# RearBreakoutSchematic.net
KiCad netlist of a schematic drawn in Altium Designer
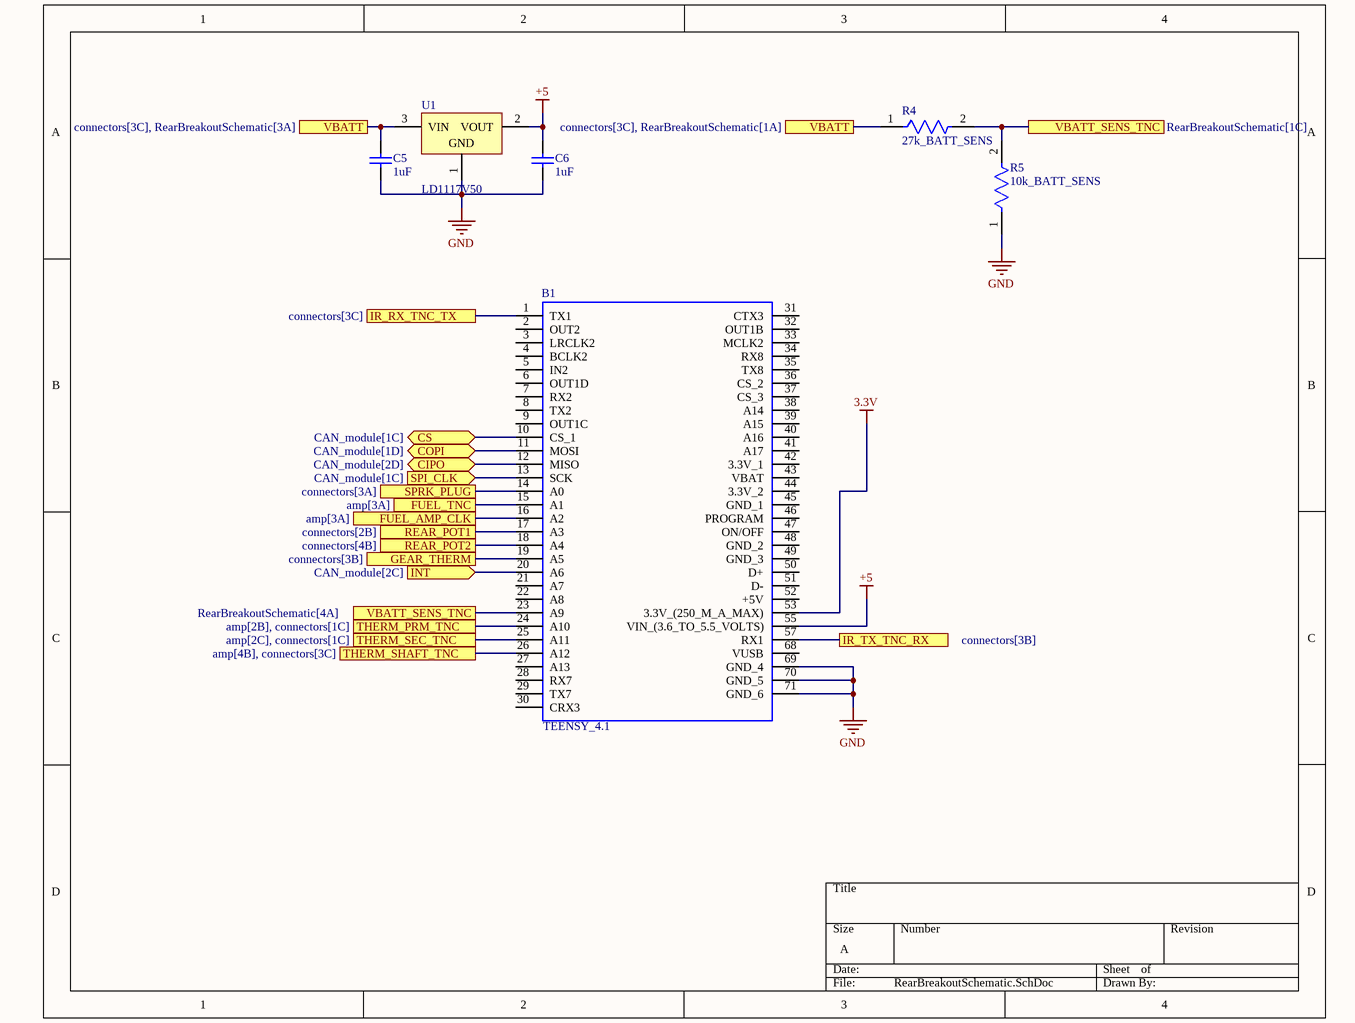
[diagram p0: RearBreakoutSchematic.SchDoc]

(export (version "E")
  (design (tool "Eeschema 10.0.6"))
  (components
    (comp (ref "B1")
      (value "TEENSY_4.1")
      (footprint "TEENSY41")
      (description "Teensy 4.1 Development Board")
      (fields (field (name "MANUFACTURER_PART_NUMBER") "TEENSY 4.1"))
      (libsource (lib "TEENSY_4.1") (part "TEENSY_4.1"))
    )
    (comp (ref "C5")
      (value "1uF")
      (footprint "CAPC2013X145X50LL20T25")
      (description "C0805C105K4PACTU")
      (fields (field (name "MANUFACTURER") "Kemet"))
      (libsource (lib "Altium Content Vault") (part "CAP"))
    )
    (comp (ref "C6")
      (value "1uF")
      (footprint "CAPC2013X145X50LL20T25")
      (description "C0805C105K4PACTU")
      (fields (field (name "MANUFACTURER") "Kemet"))
      (libsource (lib "Altium Content Vault") (part "CAP"))
    )
    (comp (ref "R4")
      (value "27k_BATT_SENS")
      (footprint "FP-CRCW0805-e3-IPC_C")
      (description "RES Thick Film, 4.02Ω, 1%, 0.125W, 200ppm/°C, 0805")
      (fields (field (name "TOLERANCE") "1%"))
      (libsource (lib "Altium Content Vault") (part "1029c3af85768c4190bb7ad29bc67b5"))
    )
    (comp (ref "R5")
      (value "10k_BATT_SENS")
      (footprint "FP-CRCW0805-e3-IPC_C")
      (description "RES Thick Film, 4.02Ω, 1%, 0.125W, 200ppm/°C, 0805")
      (fields (field (name "TOLERANCE") "1%"))
      (libsource (lib "Altium Content Vault") (part "1029c3af85768c4190bb7ad29bc67b5"))
    )
    (comp (ref "U1")
      (value "LD1117V50")
      (footprint "TO220")
      (description "Fixed Low Drop Positive Voltage Regulator, 5V, 3-Pin TO-220")
      (libsource (lib "Altium Content Vault") (part "PM-REG-LD1117V-SIL3"))
    )
  )
  (nets
    (net (code "1") (name "+5") (class "Default")
      (node (ref "B1") (pin "55") (pinfunction "VIN_(3.6_TO_5.5_VOLTS)_55") (pintype "passive"))
      (node (ref "C6") (pin "2") (pinfunction "2_2") (pintype "passive"))
      (node (ref "U1") (pin "2") (pinfunction "VOUT_2") (pintype "power_in"))
    )
    (net (code "2") (name "/CIPO") (class "Default")
      (node (ref "B1") (pin "12") (pinfunction "MISO_12") (pintype "passive"))
    )
    (net (code "3") (name "/COPI") (class "Default")
      (node (ref "B1") (pin "11") (pinfunction "MOSI_11") (pintype "passive"))
    )
    (net (code "4") (name "/CS") (class "Default")
      (node (ref "B1") (pin "10") (pinfunction "CS_1_10") (pintype "passive"))
    )
    (net (code "5") (name "/FUEL_AMP_CLK") (class "Default")
      (node (ref "B1") (pin "16") (pinfunction "A2_16") (pintype "passive"))
    )
    (net (code "6") (name "/FUEL_TNC") (class "Default")
      (node (ref "B1") (pin "15") (pinfunction "A1_15") (pintype "passive"))
    )
    (net (code "7") (name "/GEAR_THERM") (class "Default")
      (node (ref "B1") (pin "19") (pinfunction "A5_19") (pintype "passive"))
    )
    (net (code "8") (name "/INT") (class "Default")
      (node (ref "B1") (pin "20") (pinfunction "A6_20") (pintype "passive"))
    )
    (net (code "9") (name "/IR_RX_TNC_TX") (class "Default")
      (node (ref "B1") (pin "1") (pinfunction "TX1_1") (pintype "passive"))
    )
    (net (code "10") (name "/IR_TX_TNC_RX") (class "Default")
      (node (ref "B1") (pin "57") (pinfunction "RX1_57") (pintype "passive"))
    )
    (net (code "11") (name "/REAR_POT1") (class "Default")
      (node (ref "B1") (pin "17") (pinfunction "A3_17") (pintype "passive"))
    )
    (net (code "12") (name "/REAR_POT2") (class "Default")
      (node (ref "B1") (pin "18") (pinfunction "A4_18") (pintype "passive"))
    )
    (net (code "13") (name "/SPI_CLK") (class "Default")
      (node (ref "B1") (pin "13") (pinfunction "SCK_13") (pintype "passive"))
    )
    (net (code "14") (name "/SPRK_PLUG") (class "Default")
      (node (ref "B1") (pin "14") (pinfunction "A0_14") (pintype "passive"))
    )
    (net (code "15") (name "/THERM_PRM_TNC") (class "Default")
      (node (ref "B1") (pin "24") (pinfunction "A10_24") (pintype "passive"))
    )
    (net (code "16") (name "/THERM_SEC_TNC") (class "Default")
      (node (ref "B1") (pin "25") (pinfunction "A11_25") (pintype "passive"))
    )
    (net (code "17") (name "/THERM_SHAFT_TNC") (class "Default")
      (node (ref "B1") (pin "26") (pinfunction "A12_26") (pintype "passive"))
    )
    (net (code "18") (name "/VBATT") (class "Default")
      (node (ref "C5") (pin "2") (pinfunction "2_2") (pintype "passive"))
      (node (ref "R4") (pin "1") (pinfunction "1_1") (pintype "passive"))
      (node (ref "U1") (pin "3") (pinfunction "VIN_3") (pintype "power_in"))
    )
    (net (code "19") (name "/VBATT_SENS_TNC") (class "Default")
      (node (ref "B1") (pin "23") (pinfunction "A9_23") (pintype "passive"))
      (node (ref "R4") (pin "2") (pinfunction "2_2") (pintype "passive"))
      (node (ref "R5") (pin "2") (pinfunction "2_2") (pintype "passive"))
    )
    (net (code "20") (name "3.3V") (class "Default")
      (node (ref "B1") (pin "53") (pinfunction "3.3V_(250_M_A_MAX)_53") (pintype "passive"))
    )
    (net (code "21") (name "GND") (class "Default")
      (node (ref "B1") (pin "69") (pinfunction "GND_4_69") (pintype "passive"))
      (node (ref "B1") (pin "70") (pinfunction "GND_5_70") (pintype "passive"))
      (node (ref "B1") (pin "71") (pinfunction "GND_6_71") (pintype "passive"))
      (node (ref "C5") (pin "1") (pinfunction "1_1") (pintype "passive"))
      (node (ref "C6") (pin "1") (pinfunction "1_1") (pintype "passive"))
      (node (ref "R5") (pin "1") (pinfunction "1_1") (pintype "passive"))
      (node (ref "U1") (pin "1") (pinfunction "GND_1") (pintype "power_in"))
    )
    (net (code "22") (name "unconnected-(B1-+5V-Pad52)") (class "Default")
      (node (ref "B1") (pin "52") (pinfunction "+5V_52") (pintype "passive"))
    )
    (net (code "23") (name "unconnected-(B1-3.3V_1-Pad42)") (class "Default")
      (node (ref "B1") (pin "42") (pinfunction "3.3V_1_42") (pintype "passive"))
    )
    (net (code "24") (name "unconnected-(B1-3.3V_2-Pad44)") (class "Default")
      (node (ref "B1") (pin "44") (pinfunction "3.3V_2_44") (pintype "passive"))
    )
    (net (code "25") (name "unconnected-(B1-A7-Pad21)") (class "Default")
      (node (ref "B1") (pin "21") (pinfunction "A7_21") (pintype "passive"))
    )
    (net (code "26") (name "unconnected-(B1-A8-Pad22)") (class "Default")
      (node (ref "B1") (pin "22") (pinfunction "A8_22") (pintype "passive"))
    )
    (net (code "27") (name "unconnected-(B1-A13-Pad27)") (class "Default")
      (node (ref "B1") (pin "27") (pinfunction "A13_27") (pintype "passive"))
    )
    (net (code "28") (name "unconnected-(B1-A14-Pad38)") (class "Default")
      (node (ref "B1") (pin "38") (pinfunction "A14_38") (pintype "passive"))
    )
    (net (code "29") (name "unconnected-(B1-A15-Pad39)") (class "Default")
      (node (ref "B1") (pin "39") (pinfunction "A15_39") (pintype "passive"))
    )
    (net (code "30") (name "unconnected-(B1-A16-Pad40)") (class "Default")
      (node (ref "B1") (pin "40") (pinfunction "A16_40") (pintype "passive"))
    )
    (net (code "31") (name "unconnected-(B1-A17-Pad41)") (class "Default")
      (node (ref "B1") (pin "41") (pinfunction "A17_41") (pintype "passive"))
    )
    (net (code "32") (name "unconnected-(B1-BCLK2-Pad4)") (class "Default")
      (node (ref "B1") (pin "4") (pinfunction "BCLK2_4") (pintype "passive"))
    )
    (net (code "33") (name "unconnected-(B1-CRX3-Pad30)") (class "Default")
      (node (ref "B1") (pin "30") (pinfunction "CRX3_30") (pintype "passive"))
    )
    (net (code "34") (name "unconnected-(B1-CS_2-Pad36)") (class "Default")
      (node (ref "B1") (pin "36") (pinfunction "CS_2_36") (pintype "passive"))
    )
    (net (code "35") (name "unconnected-(B1-CS_3-Pad37)") (class "Default")
      (node (ref "B1") (pin "37") (pinfunction "CS_3_37") (pintype "passive"))
    )
    (net (code "36") (name "unconnected-(B1-CTX3-Pad31)") (class "Default")
      (node (ref "B1") (pin "31") (pinfunction "CTX3_31") (pintype "passive"))
    )
    (net (code "37") (name "unconnected-(B1-D+-Pad50)") (class "Default")
      (node (ref "B1") (pin "50") (pinfunction "D+_50") (pintype "passive"))
    )
    (net (code "38") (name "unconnected-(B1-D--Pad51)") (class "Default")
      (node (ref "B1") (pin "51") (pinfunction "D-_51") (pintype "passive"))
    )
    (net (code "39") (name "unconnected-(B1-GND_1-Pad45)") (class "Default")
      (node (ref "B1") (pin "45") (pinfunction "GND_1_45") (pintype "passive"))
    )
    (net (code "40") (name "unconnected-(B1-GND_2-Pad48)") (class "Default")
      (node (ref "B1") (pin "48") (pinfunction "GND_2_48") (pintype "passive"))
    )
    (net (code "41") (name "unconnected-(B1-GND_3-Pad49)") (class "Default")
      (node (ref "B1") (pin "49") (pinfunction "GND_3_49") (pintype "passive"))
    )
    (net (code "42") (name "unconnected-(B1-IN2-Pad5)") (class "Default")
      (node (ref "B1") (pin "5") (pinfunction "IN2_5") (pintype "passive"))
    )
    (net (code "43") (name "unconnected-(B1-LRCLK2-Pad3)") (class "Default")
      (node (ref "B1") (pin "3") (pinfunction "LRCLK2_3") (pintype "passive"))
    )
    (net (code "44") (name "unconnected-(B1-MCLK2-Pad33)") (class "Default")
      (node (ref "B1") (pin "33") (pinfunction "MCLK2_33") (pintype "passive"))
    )
    (net (code "45") (name "unconnected-(B1-ON{slash}OFF-Pad47)") (class "Default")
      (node (ref "B1") (pin "47") (pinfunction "ON/OFF_47") (pintype "passive"))
    )
    (net (code "46") (name "unconnected-(B1-OUT1B-Pad32)") (class "Default")
      (node (ref "B1") (pin "32") (pinfunction "OUT1B_32") (pintype "passive"))
    )
    (net (code "47") (name "unconnected-(B1-OUT1C-Pad9)") (class "Default")
      (node (ref "B1") (pin "9") (pinfunction "OUT1C_9") (pintype "passive"))
    )
    (net (code "48") (name "unconnected-(B1-OUT1D-Pad6)") (class "Default")
      (node (ref "B1") (pin "6") (pinfunction "OUT1D_6") (pintype "passive"))
    )
    (net (code "49") (name "unconnected-(B1-OUT2-Pad2)") (class "Default")
      (node (ref "B1") (pin "2") (pinfunction "OUT2_2") (pintype "passive"))
    )
    (net (code "50") (name "unconnected-(B1-PROGRAM-Pad46)") (class "Default")
      (node (ref "B1") (pin "46") (pinfunction "PROGRAM_46") (pintype "passive"))
    )
    (net (code "51") (name "unconnected-(B1-RX2-Pad7)") (class "Default")
      (node (ref "B1") (pin "7") (pinfunction "RX2_7") (pintype "passive"))
    )
    (net (code "52") (name "unconnected-(B1-RX7-Pad28)") (class "Default")
      (node (ref "B1") (pin "28") (pinfunction "RX7_28") (pintype "passive"))
    )
    (net (code "53") (name "unconnected-(B1-RX8-Pad34)") (class "Default")
      (node (ref "B1") (pin "34") (pinfunction "RX8_34") (pintype "passive"))
    )
    (net (code "54") (name "unconnected-(B1-TX2-Pad8)") (class "Default")
      (node (ref "B1") (pin "8") (pinfunction "TX2_8") (pintype "passive"))
    )
    (net (code "55") (name "unconnected-(B1-TX7-Pad29)") (class "Default")
      (node (ref "B1") (pin "29") (pinfunction "TX7_29") (pintype "passive"))
    )
    (net (code "56") (name "unconnected-(B1-TX8-Pad35)") (class "Default")
      (node (ref "B1") (pin "35") (pinfunction "TX8_35") (pintype "passive"))
    )
    (net (code "57") (name "unconnected-(B1-VBAT-Pad43)") (class "Default")
      (node (ref "B1") (pin "43") (pinfunction "VBAT_43") (pintype "passive"))
    )
    (net (code "58") (name "unconnected-(B1-VUSB-Pad68)") (class "Default")
      (node (ref "B1") (pin "68") (pinfunction "VUSB_68") (pintype "passive"))
    )
  )
)
